# Relays.net
KiCad netlist of a schematic drawn in Altium Designer
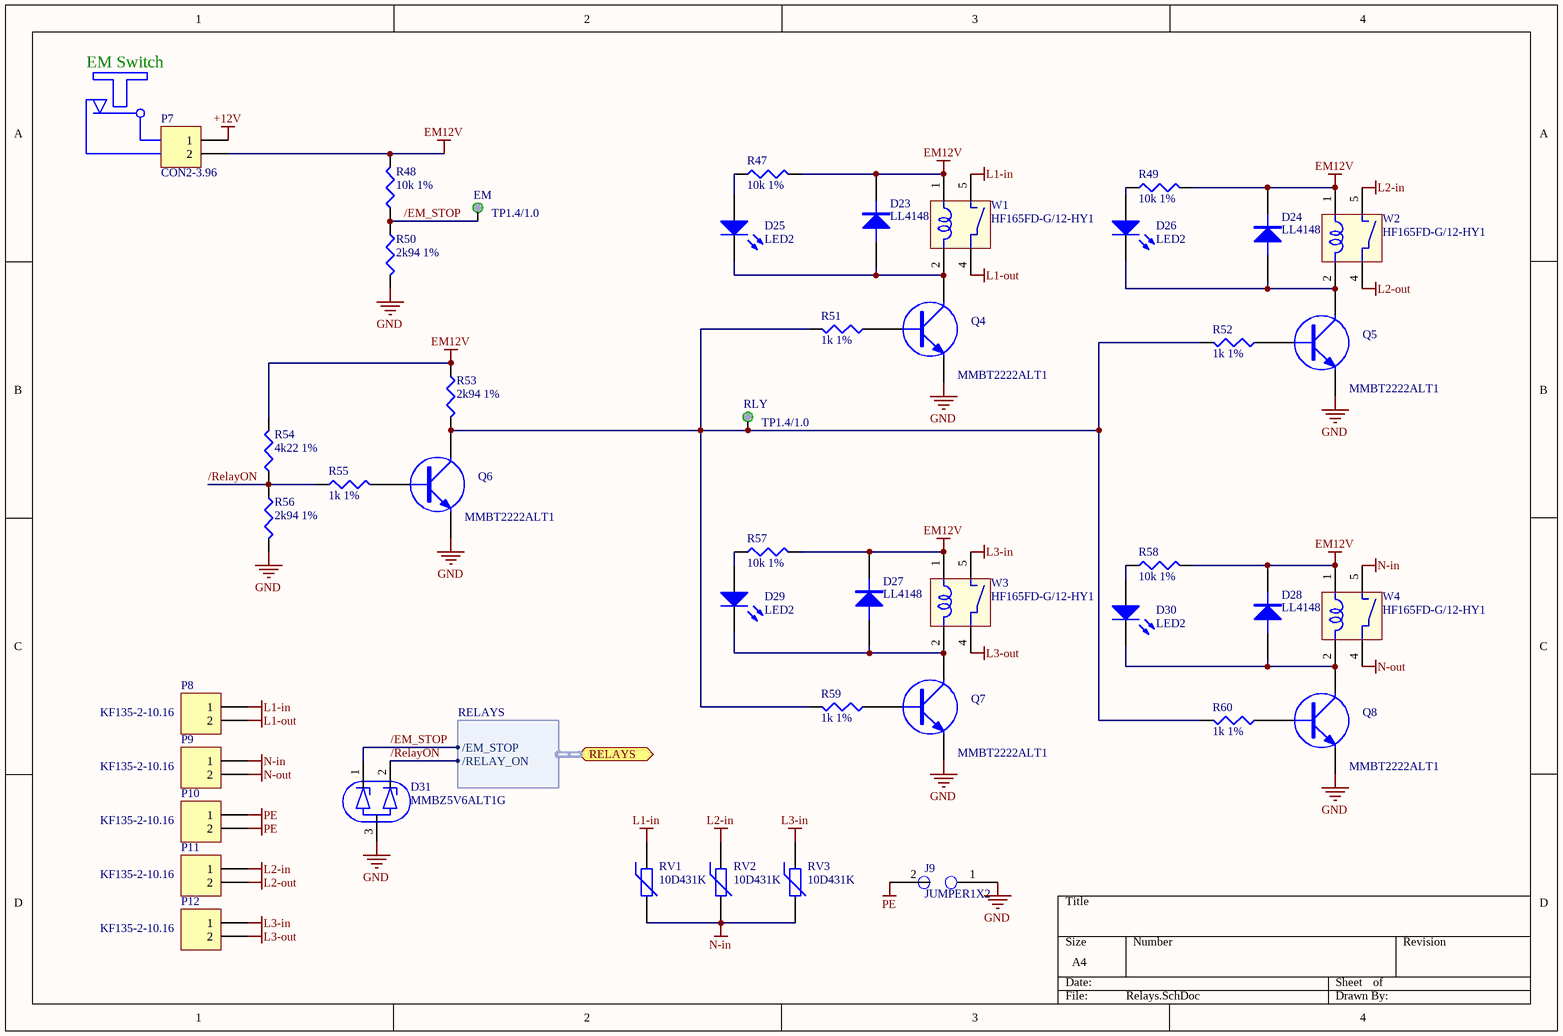
[diagram p0: Relays.SchDoc]

(export (version "E")
  (design (tool "Eeschema 10.0.6"))
  (components
    (comp (ref "D23")
      (value "LL4148")
      (footprint "MELF - Diode:MELF-D3513-1405")
      (description "Diode")
      (libsource (lib "*") (part "DIODE"))
    )
    (comp (ref "D24")
      (value "LL4148")
      (footprint "MELF - Diode:MELF-D3513-1405")
      (description "Diode")
      (libsource (lib "*") (part "DIODE"))
    )
    (comp (ref "D25")
      (value "LED2")
      (footprint "3.2X1.6X1.1")
      (description "Typical RED, GREEN, YELLOW, AMBER GaAs LED")
      (fields (field (name "PUBLISHER") "Altium Limited"))
      (libsource (lib "Miscellaneous Devices") (part "LED2"))
    )
    (comp (ref "D26")
      (value "LED2")
      (footprint "3.2X1.6X1.1")
      (description "Typical RED, GREEN, YELLOW, AMBER GaAs LED")
      (fields (field (name "PUBLISHER") "Altium Limited"))
      (libsource (lib "Miscellaneous Devices") (part "LED2"))
    )
    (comp (ref "D27")
      (value "LL4148")
      (footprint "MELF - Diode:MELF-D3513-1405")
      (description "Diode")
      (libsource (lib "*") (part "DIODE"))
    )
    (comp (ref "D28")
      (value "LL4148")
      (footprint "MELF - Diode:MELF-D3513-1405")
      (description "Diode")
      (libsource (lib "*") (part "DIODE"))
    )
    (comp (ref "D29")
      (value "LED2")
      (footprint "3.2X1.6X1.1")
      (description "Typical RED, GREEN, YELLOW, AMBER GaAs LED")
      (fields (field (name "PUBLISHER") "Altium Limited"))
      (libsource (lib "Miscellaneous Devices") (part "LED2"))
    )
    (comp (ref "D30")
      (value "LED2")
      (footprint "3.2X1.6X1.1")
      (description "Typical RED, GREEN, YELLOW, AMBER GaAs LED")
      (fields (field (name "PUBLISHER") "Altium Limited"))
      (libsource (lib "Miscellaneous Devices") (part "LED2"))
    )
    (comp (ref "D31")
      (value "MMBZ5V6ALT1G")
      (footprint "SOT23_N:SOT23-3N")
      (description "ESD protection diode 3.3V")
      (fields (field (name "MANUFACTURER") "NXP"))
      (libsource (lib "UserSchlib") (part "PESD3V3S2UT"))
    )
    (comp (ref "EM")
      (value "TP1.4/1.0")
      (footprint "UserPcbLib:TP1.4/1.0")
      (libsource (lib "UserSchlib") (part "TP1.4/1.0"))
    )
    (comp (ref "J9")
      (value "JUMPER1X2")
      (footprint "UserPcbLib:JP-SOLDER-H1X2-3X2")
      (libsource (lib "Peter") (part "JUMPER1X2"))
    )
    (comp (ref "P7")
      (value "CON2-3.96")
      (footprint "UserPcbLib:CON2/3.96mm")
      (description "Header, 2-Pin")
      (fields (field (name "PUBLISHER") "Altium Limited"))
      (libsource (lib "Miscellaneous Connectors") (part "Header 2"))
    )
    (comp (ref "P8")
      (value "KF135-2-10.16")
      (footprint "UserPcbLib:KF135-2-10.16")
      (fields (field (name "PUBLISHER") "Altium Limited"))
      (libsource (lib "Miscellaneous Connectors") (part "Header 2"))
    )
    (comp (ref "P9")
      (value "KF135-2-10.16")
      (footprint "UserPcbLib:KF135-2-10.16")
      (fields (field (name "PUBLISHER") "Altium Limited"))
      (libsource (lib "Miscellaneous Connectors") (part "Header 2"))
    )
    (comp (ref "P10")
      (value "KF135-2-10.16")
      (footprint "UserPcbLib:KF135-2-10.16")
      (fields (field (name "PUBLISHER") "Altium Limited"))
      (libsource (lib "Miscellaneous Connectors") (part "Header 2"))
    )
    (comp (ref "P11")
      (value "KF135-2-10.16")
      (footprint "UserPcbLib:KF135-2-10.16")
      (fields (field (name "PUBLISHER") "Altium Limited"))
      (libsource (lib "Miscellaneous Connectors") (part "Header 2"))
    )
    (comp (ref "P12")
      (value "KF135-2-10.16")
      (footprint "UserPcbLib:KF135-2-10.16")
      (fields (field (name "PUBLISHER") "Altium Limited"))
      (libsource (lib "Miscellaneous Connectors") (part "Header 2"))
    )
    (comp (ref "Q4")
      (value "MMBT2222ALT1")
      (footprint "SOT23_N:SOT23-3N")
      (description "NPN transistor")
      (libsource (lib "*") (part "NPN"))
    )
    (comp (ref "Q5")
      (value "MMBT2222ALT1")
      (footprint "SOT23_N:SOT23-3N")
      (description "NPN transistor")
      (libsource (lib "*") (part "NPN"))
    )
    (comp (ref "Q6")
      (value "MMBT2222ALT1")
      (footprint "SOT23_N:SOT23-3N")
      (description "NPN transistor")
      (libsource (lib "*") (part "NPN"))
    )
    (comp (ref "Q7")
      (value "MMBT2222ALT1")
      (footprint "SOT23_N:SOT23-3N")
      (description "NPN transistor")
      (libsource (lib "*") (part "NPN"))
    )
    (comp (ref "Q8")
      (value "MMBT2222ALT1")
      (footprint "SOT23_N:SOT23-3N")
      (description "NPN transistor")
      (libsource (lib "*") (part "NPN"))
    )
    (comp (ref "R47")
      (value "10k 1%")
      (footprint "IPC-7352 Chip_Resistor_N:RESC2012N")
      (description "Resistor")
      (libsource (lib "Miscellaneous Devices") (part "Res3"))
    )
    (comp (ref "R48")
      (value "10k 1%")
      (footprint "IPC-7352 Chip_Resistor_N:RESC2012N")
      (description "Resistor")
      (libsource (lib "Miscellaneous Devices") (part "Res3"))
    )
    (comp (ref "R49")
      (value "10k 1%")
      (footprint "IPC-7352 Chip_Resistor_N:RESC2012N")
      (description "Resistor")
      (libsource (lib "Miscellaneous Devices") (part "Res3"))
    )
    (comp (ref "R50")
      (value "2k94 1%")
      (footprint "IPC-7352 Chip_Resistor_N:RESC2012N")
      (description "Resistor")
      (libsource (lib "Miscellaneous Devices") (part "Res3"))
    )
    (comp (ref "R51")
      (value "1k 1%")
      (footprint "IPC-7352 Chip_Resistor_N:RESC2012N")
      (description "Resistor")
      (libsource (lib "Miscellaneous Devices") (part "Res3"))
    )
    (comp (ref "R52")
      (value "1k 1%")
      (footprint "IPC-7352 Chip_Resistor_N:RESC2012N")
      (description "Resistor")
      (libsource (lib "Miscellaneous Devices") (part "Res3"))
    )
    (comp (ref "R53")
      (value "2k94 1%")
      (footprint "IPC-7352 Chip_Resistor_N:RESC2012N")
      (description "Resistor")
      (libsource (lib "Miscellaneous Devices") (part "Res3"))
    )
    (comp (ref "R54")
      (value "4k22 1%")
      (footprint "IPC-7352 Chip_Resistor_N:RESC2012N")
      (description "Resistor")
      (libsource (lib "Miscellaneous Devices") (part "Res3"))
    )
    (comp (ref "R55")
      (value "1k 1%")
      (footprint "IPC-7352 Chip_Resistor_N:RESC2012N")
      (description "Resistor")
      (libsource (lib "Miscellaneous Devices") (part "Res3"))
    )
    (comp (ref "R56")
      (value "2k94 1%")
      (footprint "IPC-7352 Chip_Resistor_N:RESC2012N")
      (description "Resistor")
      (libsource (lib "Miscellaneous Devices") (part "Res3"))
    )
    (comp (ref "R57")
      (value "10k 1%")
      (footprint "IPC-7352 Chip_Resistor_N:RESC2012N")
      (description "Resistor")
      (libsource (lib "Miscellaneous Devices") (part "Res3"))
    )
    (comp (ref "R58")
      (value "10k 1%")
      (footprint "IPC-7352 Chip_Resistor_N:RESC2012N")
      (description "Resistor")
      (libsource (lib "Miscellaneous Devices") (part "Res3"))
    )
    (comp (ref "R59")
      (value "1k 1%")
      (footprint "IPC-7352 Chip_Resistor_N:RESC2012N")
      (description "Resistor")
      (libsource (lib "Miscellaneous Devices") (part "Res3"))
    )
    (comp (ref "R60")
      (value "1k 1%")
      (footprint "IPC-7352 Chip_Resistor_N:RESC2012N")
      (description "Resistor")
      (libsource (lib "Miscellaneous Devices") (part "Res3"))
    )
    (comp (ref "RLY")
      (value "TP1.4/1.0")
      (footprint "UserPcbLib:TP1.4/1.0")
      (libsource (lib "UserSchlib") (part "TP1.4/1.0"))
    )
    (comp (ref "RV1")
      (value "10D431K")
      (footprint "UserPcbLib:10D431K")
      (description "Varistor (Voltage-Sensitive Resistor)")
      (fields (field (name "PUBLISHER") "Altium Limited"))
      (libsource (lib "Miscellaneous Devices") (part "Res Varistor"))
    )
    (comp (ref "RV2")
      (value "10D431K")
      (footprint "UserPcbLib:10D431K")
      (description "Varistor (Voltage-Sensitive Resistor)")
      (fields (field (name "PUBLISHER") "Altium Limited"))
      (libsource (lib "Miscellaneous Devices") (part "Res Varistor"))
    )
    (comp (ref "RV3")
      (value "10D431K")
      (footprint "UserPcbLib:10D431K")
      (description "Varistor (Voltage-Sensitive Resistor)")
      (fields (field (name "PUBLISHER") "Altium Limited"))
      (libsource (lib "Miscellaneous Devices") (part "Res Varistor"))
    )
    (comp (ref "W1")
      (value "HF165FD-G/12-HY1")
      (footprint "UserPcbLib:HF165FD-G/12-HY1")
      (description "Hongfa power relay 40A")
      (libsource (lib "UserSchlib") (part "HF165FD-G/12-HY1"))
    )
    (comp (ref "W2")
      (value "HF165FD-G/12-HY1")
      (footprint "UserPcbLib:HF165FD-G/12-HY1")
      (description "Hongfa power relay 40A")
      (libsource (lib "UserSchlib") (part "HF165FD-G/12-HY1"))
    )
    (comp (ref "W3")
      (value "HF165FD-G/12-HY1")
      (footprint "UserPcbLib:HF165FD-G/12-HY1")
      (description "Hongfa power relay 40A")
      (libsource (lib "UserSchlib") (part "HF165FD-G/12-HY1"))
    )
    (comp (ref "W4")
      (value "HF165FD-G/12-HY1")
      (footprint "UserPcbLib:HF165FD-G/12-HY1")
      (description "Hongfa power relay 40A")
      (libsource (lib "UserSchlib") (part "HF165FD-G/12-HY1"))
    )
  )
  (nets
    (net (code "2") (name "+12V") (class "Default")
      (node (ref "P7") (pin "1") (pinfunction "1_1") (pintype "passive"))
    )
    (net (code "4") (name "/{slash}EM_STOP") (class "Default")
      (node (ref "D31") (pin "1") (pinfunction "1_1") (pintype "passive"))
      (node (ref "EM") (pin "1") (pinfunction "1_1") (pintype "passive"))
      (node (ref "R48") (pin "1") (pinfunction "1_1") (pintype "passive"))
      (node (ref "R50") (pin "1") (pinfunction "1_1") (pintype "passive"))
    )
    (net (code "5") (name "/{slash}RelayON") (class "Default")
      (node (ref "D31") (pin "2") (pinfunction "2_2") (pintype "passive"))
      (node (ref "R54") (pin "1") (pinfunction "1_1") (pintype "passive"))
      (node (ref "R55") (pin "1") (pinfunction "1_1") (pintype "passive"))
      (node (ref "R56") (pin "1") (pinfunction "1_1") (pintype "passive"))
    )
    (net (code "6") (name "EM12V") (class "Default")
      (node (ref "D23") (pin "2") (pinfunction "K_2") (pintype "passive"))
      (node (ref "D24") (pin "2") (pinfunction "K_2") (pintype "passive"))
      (node (ref "D27") (pin "2") (pinfunction "K_2") (pintype "passive"))
      (node (ref "D28") (pin "2") (pinfunction "K_2") (pintype "passive"))
      (node (ref "P7") (pin "2") (pinfunction "2_2") (pintype "passive"))
      (node (ref "R47") (pin "2") (pinfunction "2_2") (pintype "passive"))
      (node (ref "R48") (pin "2") (pinfunction "2_2") (pintype "passive"))
      (node (ref "R49") (pin "2") (pinfunction "2_2") (pintype "passive"))
      (node (ref "R53") (pin "1") (pinfunction "1_1") (pintype "passive"))
      (node (ref "R54") (pin "2") (pinfunction "2_2") (pintype "passive"))
      (node (ref "R57") (pin "2") (pinfunction "2_2") (pintype "passive"))
      (node (ref "R58") (pin "2") (pinfunction "2_2") (pintype "passive"))
      (node (ref "W1") (pin "1") (pinfunction "1_1") (pintype "passive"))
      (node (ref "W2") (pin "1") (pinfunction "1_1") (pintype "passive"))
      (node (ref "W3") (pin "1") (pinfunction "1_1") (pintype "passive"))
      (node (ref "W4") (pin "1") (pinfunction "1_1") (pintype "passive"))
    )
    (net (code "7") (name "GND") (class "Default")
      (node (ref "D31") (pin "3") (pinfunction "3_3") (pintype "passive"))
      (node (ref "J9") (pin "1") (pinfunction "0_1") (pintype "passive"))
      (node (ref "Q4") (pin "2") (pinfunction "E_2") (pintype "passive"))
      (node (ref "Q5") (pin "2") (pinfunction "E_2") (pintype "passive"))
      (node (ref "Q6") (pin "2") (pinfunction "E_2") (pintype "passive"))
      (node (ref "Q7") (pin "2") (pinfunction "E_2") (pintype "passive"))
      (node (ref "Q8") (pin "2") (pinfunction "E_2") (pintype "passive"))
      (node (ref "R50") (pin "2") (pinfunction "2_2") (pintype "passive"))
      (node (ref "R56") (pin "2") (pinfunction "2_2") (pintype "passive"))
    )
    (net (code "8") (name "L1-in") (class "Default")
      (node (ref "P8") (pin "1") (pinfunction "1_1") (pintype "passive"))
      (node (ref "RV1") (pin "1") (pinfunction "1_1") (pintype "passive"))
      (node (ref "W1") (pin "5") (pinfunction "5_5") (pintype "passive"))
    )
    (net (code "9") (name "L1-out") (class "Default")
      (node (ref "P8") (pin "2") (pinfunction "2_2") (pintype "passive"))
      (node (ref "W1") (pin "4") (pinfunction "4_4") (pintype "passive"))
    )
    (net (code "10") (name "L2-in") (class "Default")
      (node (ref "P11") (pin "1") (pinfunction "1_1") (pintype "passive"))
      (node (ref "RV2") (pin "1") (pinfunction "1_1") (pintype "passive"))
      (node (ref "W2") (pin "5") (pinfunction "5_5") (pintype "passive"))
    )
    (net (code "11") (name "L2-out") (class "Default")
      (node (ref "P11") (pin "2") (pinfunction "2_2") (pintype "passive"))
      (node (ref "W2") (pin "4") (pinfunction "4_4") (pintype "passive"))
    )
    (net (code "12") (name "L3-in") (class "Default")
      (node (ref "P12") (pin "1") (pinfunction "1_1") (pintype "passive"))
      (node (ref "RV3") (pin "1") (pinfunction "1_1") (pintype "passive"))
      (node (ref "W3") (pin "5") (pinfunction "5_5") (pintype "passive"))
    )
    (net (code "13") (name "L3-out") (class "Default")
      (node (ref "P12") (pin "2") (pinfunction "2_2") (pintype "passive"))
      (node (ref "W3") (pin "4") (pinfunction "4_4") (pintype "passive"))
    )
    (net (code "14") (name "N-in") (class "Default")
      (node (ref "P9") (pin "1") (pinfunction "1_1") (pintype "passive"))
      (node (ref "RV1") (pin "2") (pinfunction "2_2") (pintype "passive"))
      (node (ref "RV2") (pin "2") (pinfunction "2_2") (pintype "passive"))
      (node (ref "RV3") (pin "2") (pinfunction "2_2") (pintype "passive"))
      (node (ref "W4") (pin "5") (pinfunction "5_5") (pintype "passive"))
    )
    (net (code "15") (name "N-out") (class "Default")
      (node (ref "P9") (pin "2") (pinfunction "2_2") (pintype "passive"))
      (node (ref "W4") (pin "4") (pinfunction "4_4") (pintype "passive"))
    )
    (net (code "16") (name "Net-(D23-A)") (class "Default")
      (node (ref "D23") (pin "1") (pinfunction "A_1") (pintype "passive"))
      (node (ref "D25") (pin "2") (pinfunction "K_2") (pintype "passive"))
      (node (ref "Q4") (pin "3") (pinfunction "C_3") (pintype "passive"))
      (node (ref "W1") (pin "2") (pinfunction "2_2") (pintype "passive"))
    )
    (net (code "17") (name "Net-(D24-A)") (class "Default")
      (node (ref "D24") (pin "1") (pinfunction "A_1") (pintype "passive"))
      (node (ref "D26") (pin "2") (pinfunction "K_2") (pintype "passive"))
      (node (ref "Q5") (pin "3") (pinfunction "C_3") (pintype "passive"))
      (node (ref "W2") (pin "2") (pinfunction "2_2") (pintype "passive"))
    )
    (net (code "18") (name "Net-(D25-A)") (class "Default")
      (node (ref "D25") (pin "1") (pinfunction "A_1") (pintype "passive"))
      (node (ref "R47") (pin "1") (pinfunction "1_1") (pintype "passive"))
    )
    (net (code "19") (name "Net-(D26-A)") (class "Default")
      (node (ref "D26") (pin "1") (pinfunction "A_1") (pintype "passive"))
      (node (ref "R49") (pin "1") (pinfunction "1_1") (pintype "passive"))
    )
    (net (code "20") (name "Net-(D27-A)") (class "Default")
      (node (ref "D27") (pin "1") (pinfunction "A_1") (pintype "passive"))
      (node (ref "D29") (pin "2") (pinfunction "K_2") (pintype "passive"))
      (node (ref "Q7") (pin "3") (pinfunction "C_3") (pintype "passive"))
      (node (ref "W3") (pin "2") (pinfunction "2_2") (pintype "passive"))
    )
    (net (code "21") (name "Net-(D28-A)") (class "Default")
      (node (ref "D28") (pin "1") (pinfunction "A_1") (pintype "passive"))
      (node (ref "D30") (pin "2") (pinfunction "K_2") (pintype "passive"))
      (node (ref "Q8") (pin "3") (pinfunction "C_3") (pintype "passive"))
      (node (ref "W4") (pin "2") (pinfunction "2_2") (pintype "passive"))
    )
    (net (code "22") (name "Net-(D29-A)") (class "Default")
      (node (ref "D29") (pin "1") (pinfunction "A_1") (pintype "passive"))
      (node (ref "R57") (pin "1") (pinfunction "1_1") (pintype "passive"))
    )
    (net (code "23") (name "Net-(D30-A)") (class "Default")
      (node (ref "D30") (pin "1") (pinfunction "A_1") (pintype "passive"))
      (node (ref "R58") (pin "1") (pinfunction "1_1") (pintype "passive"))
    )
    (net (code "24") (name "Net-(Q4-B)") (class "Default")
      (node (ref "Q4") (pin "1") (pinfunction "B_1") (pintype "passive"))
      (node (ref "R51") (pin "1") (pinfunction "1_1") (pintype "passive"))
    )
    (net (code "25") (name "Net-(Q5-B)") (class "Default")
      (node (ref "Q5") (pin "1") (pinfunction "B_1") (pintype "passive"))
      (node (ref "R52") (pin "1") (pinfunction "1_1") (pintype "passive"))
    )
    (net (code "26") (name "Net-(Q6-B)") (class "Default")
      (node (ref "Q6") (pin "1") (pinfunction "B_1") (pintype "passive"))
      (node (ref "R55") (pin "2") (pinfunction "2_2") (pintype "passive"))
    )
    (net (code "27") (name "Net-(Q6-C)") (class "Default")
      (node (ref "Q6") (pin "3") (pinfunction "C_3") (pintype "passive"))
      (node (ref "R51") (pin "2") (pinfunction "2_2") (pintype "passive"))
      (node (ref "R52") (pin "2") (pinfunction "2_2") (pintype "passive"))
      (node (ref "R53") (pin "2") (pinfunction "2_2") (pintype "passive"))
      (node (ref "R59") (pin "2") (pinfunction "2_2") (pintype "passive"))
      (node (ref "R60") (pin "2") (pinfunction "2_2") (pintype "passive"))
      (node (ref "RLY") (pin "1") (pinfunction "1_1") (pintype "passive"))
    )
    (net (code "28") (name "Net-(Q7-B)") (class "Default")
      (node (ref "Q7") (pin "1") (pinfunction "B_1") (pintype "passive"))
      (node (ref "R59") (pin "1") (pinfunction "1_1") (pintype "passive"))
    )
    (net (code "29") (name "Net-(Q8-B)") (class "Default")
      (node (ref "Q8") (pin "1") (pinfunction "B_1") (pintype "passive"))
      (node (ref "R60") (pin "1") (pinfunction "1_1") (pintype "passive"))
    )
    (net (code "30") (name "PE") (class "Default")
      (node (ref "J9") (pin "2") (pinfunction "1_2") (pintype "passive"))
      (node (ref "P10") (pin "1") (pinfunction "1_1") (pintype "passive"))
      (node (ref "P10") (pin "2") (pinfunction "2_2") (pintype "passive"))
    )
  )
)
